# GRHV_double_30v.net
KiCad netlist of a schematic drawn in Altium Designer
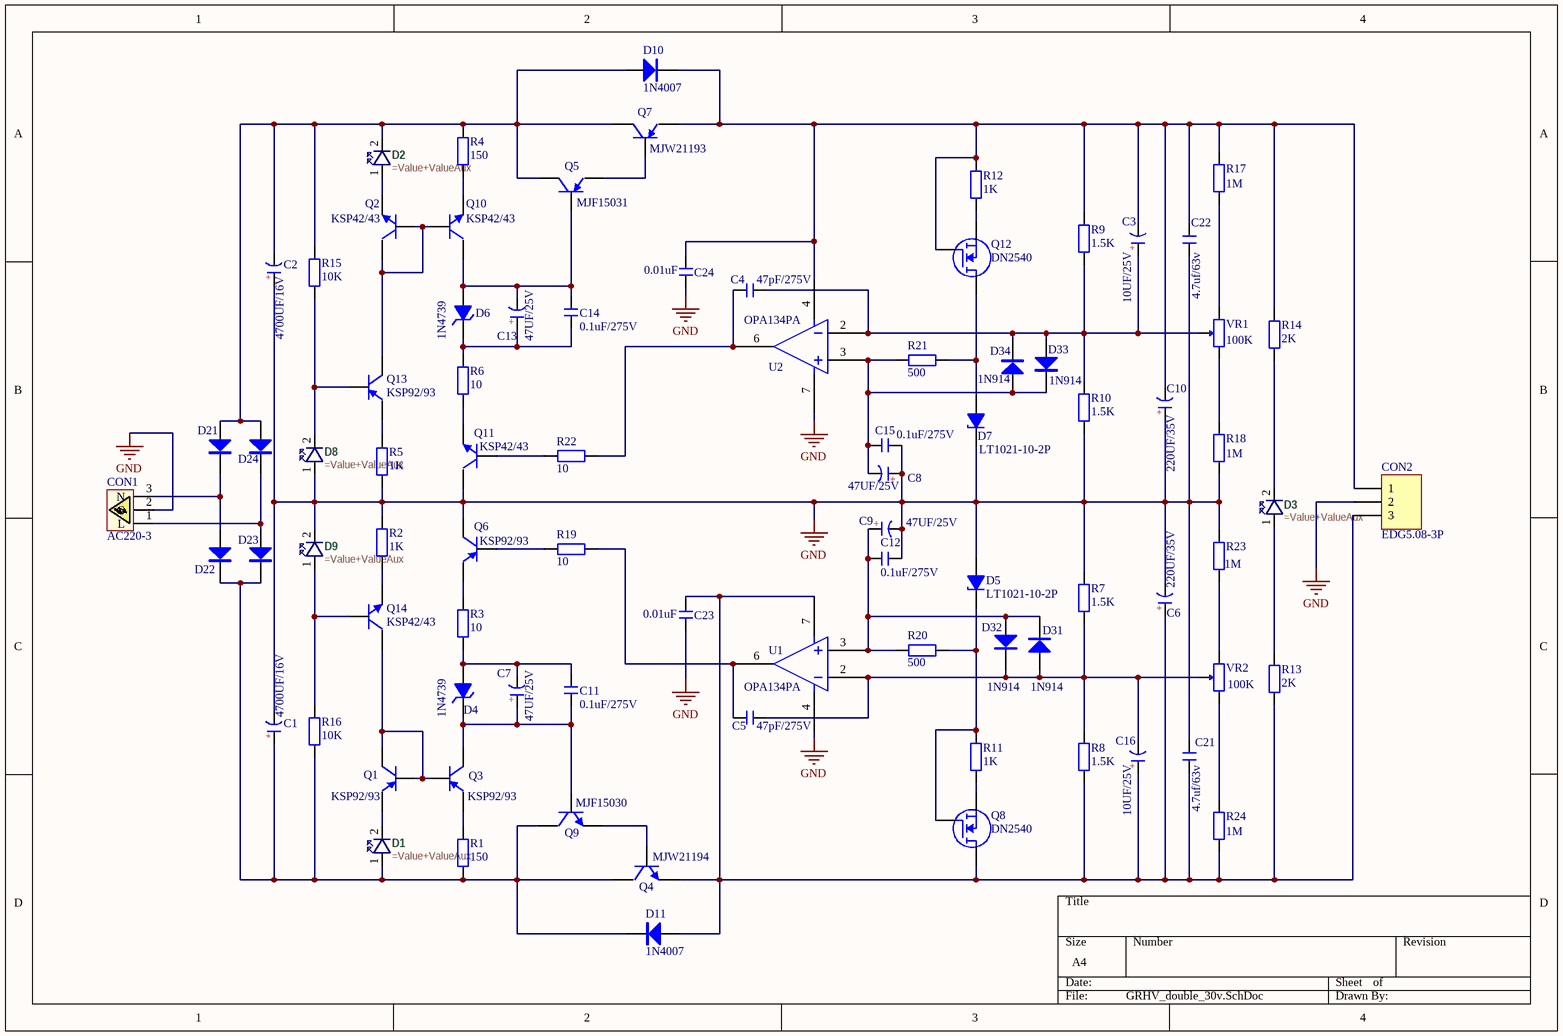
[diagram p0: GRHV_double_30v.SchDoc]

(export (version "E")
  (design (tool "Eeschema 10.0.6"))
  (components
    (comp (ref "C1")
      (value "4700UF/16V")
      (footprint "CAP 10*22*40")
      (description "直插电解电容")
      (fields (field (name "版权归属") "源创客"))
      (libsource (lib "电阻-电容-电感") (part "C-CAP"))
    )
    (comp (ref "C2")
      (value "4700UF/16V")
      (footprint "CAP 10*22*40")
      (description "直插电解电容")
      (fields (field (name "版权归属") "源创客"))
      (libsource (lib "电阻-电容-电感") (part "C-CAP"))
    )
    (comp (ref "C3")
      (value "10UF/25V")
      (footprint "CAP 2.5*6.3*7")
      (description "直插电解电容")
      (fields (field (name "版权归属") "源创客"))
      (libsource (lib "电阻-电容-电感") (part "C-CAP"))
    )
    (comp (ref "C4")
      (value "47pF/275V")
      (footprint "CBB 6.3*6.3*5")
      (description "CBB电容")
      (fields (field (name "版权归属") "源创客"))
      (libsource (lib "电阻-电容-电感") (part "C-CBB"))
    )
    (comp (ref "C5")
      (value "47pF/275V")
      (footprint "CBB 6.3*6.3*5")
      (description "CBB电容")
      (fields (field (name "版权归属") "源创客"))
      (libsource (lib "电阻-电容-电感") (part "C-CBB"))
    )
    (comp (ref "C6")
      (value "220UF/35V")
      (footprint "CAP 3.5*8*11.5")
      (description "直插电解电容")
      (fields (field (name "版权归属") "源创客"))
      (libsource (lib "电阻-电容-电感") (part "C-CAP"))
    )
    (comp (ref "C7")
      (value "47UF/25V")
      (footprint "CAP 2.5*6.3*11.2")
      (description "直插电解电容")
      (fields (field (name "版权归属") "源创客"))
      (libsource (lib "电阻-电容-电感") (part "C-CAP"))
    )
    (comp (ref "C8")
      (value "47UF/25V")
      (footprint "CAP 2.5*6.3*11.2")
      (description "直插电解电容")
      (fields (field (name "版权归属") "源创客"))
      (libsource (lib "") (part "C-CAP_1"))
    )
    (comp (ref "C9")
      (value "47UF/25V")
      (footprint "CAP 2.5*6.3*11.2")
      (description "直插电解电容")
      (fields (field (name "版权归属") "源创客"))
      (libsource (lib "") (part "C-CAP_1"))
    )
    (comp (ref "C10")
      (value "220UF/35V")
      (footprint "CAP 3.5*8*11.5")
      (description "直插电解电容")
      (fields (field (name "版权归属") "源创客"))
      (libsource (lib "电阻-电容-电感") (part "C-CAP"))
    )
    (comp (ref "C11")
      (value "0.1uF/275V")
      (footprint "CBB 6.3*6.3*5")
      (description "CBB电容")
      (fields (field (name "版权归属") "源创客"))
      (libsource (lib "电阻-电容-电感") (part "C-CBB"))
    )
    (comp (ref "C12")
      (value "0.1uF/275V")
      (footprint "CBB 6.3*6.3*5")
      (description "CBB电容")
      (fields (field (name "版权归属") "源创客"))
      (libsource (lib "电阻-电容-电感") (part "C-CBB"))
    )
    (comp (ref "C13")
      (value "47UF/25V")
      (footprint "CAP 2.5*6.3*11.2")
      (description "直插电解电容")
      (fields (field (name "版权归属") "源创客"))
      (libsource (lib "电阻-电容-电感") (part "C-CAP"))
    )
    (comp (ref "C14")
      (value "0.1uF/275V")
      (footprint "CBB 6.3*6.3*5")
      (description "CBB电容")
      (fields (field (name "版权归属") "源创客"))
      (libsource (lib "电阻-电容-电感") (part "C-CBB"))
    )
    (comp (ref "C15")
      (value "0.1uF/275V")
      (footprint "CBB 6.3*6.3*5")
      (description "CBB电容")
      (fields (field (name "版权归属") "源创客"))
      (libsource (lib "电阻-电容-电感") (part "C-CBB"))
    )
    (comp (ref "C16")
      (value "10UF/25V")
      (footprint "CAP 2.5*6.3*7")
      (description "直插电解电容")
      (fields (field (name "版权归属") "源创客"))
      (libsource (lib "电阻-电容-电感") (part "C-CAP"))
    )
    (comp (ref "C21")
      (value "4.7uf/63v")
      (footprint "CBB 7.2*7.2*13")
      (description "MKS薄膜电容")
      (libsource (lib "电阻-电容-电感") (part "C-MKS"))
    )
    (comp (ref "C22")
      (value "4.7uf/63v")
      (footprint "CBB 7.2*7.2*13")
      (description "MKS薄膜电容")
      (libsource (lib "电阻-电容-电感") (part "C-MKS"))
    )
    (comp (ref "C23")
      (value "0.01uF")
      (footprint "CBB 6.3*6.3*5")
      (description "CBB电容")
      (fields (field (name "Comment") "0.01uF/275V") (field (name "版权归属") "源创客"))
      (libsource (lib "电阻-电容-电感") (part "C-CBB"))
    )
    (comp (ref "C24")
      (value "0.01uF")
      (footprint "CBB 6.3*6.3*5")
      (description "CBB电容")
      (fields (field (name "Comment") "0.01uF/275V") (field (name "版权归属") "源创客"))
      (libsource (lib "电阻-电容-电感") (part "C-CBB"))
    )
    (comp (ref "CON1")
      (value "AC220-3")
      (footprint "HX5.08-3L")
      (libsource (lib "Connectors") (part "AC220-3"))
    )
    (comp (ref "CON2")
      (value "EDG5.08-3P")
      (footprint "HX5.08-3L")
      (libsource (lib "Connectors") (part "EDG5.08-3P"))
    )
    (comp (ref "D1")
      (value "~")
      (footprint "LED 3MM-R")
      (description "直插式LED")
      (libsource (lib "LED") (part "LED"))
    )
    (comp (ref "D2")
      (value "~")
      (footprint "LED 3MM-R")
      (description "直插式LED")
      (libsource (lib "LED") (part "LED"))
    )
    (comp (ref "D3")
      (value "~")
      (footprint "LED 3MM-R")
      (description "直插式LED")
      (libsource (lib "LED") (part "LED"))
    )
    (comp (ref "D4")
      (value "1N4739")
      (footprint "DO-41")
      (description "9.1V/1W稳压管")
      (libsource (lib "二极管-整流桥") (part "1N4739"))
    )
    (comp (ref "D5")
      (value "LT1021-10-2P")
      (footprint "DIP8-300_MH")
      (description "10V Precision Reference 2 Pin Config")
      (libsource (lib "电压参考") (part "LT1021-10-2P"))
    )
    (comp (ref "D6")
      (value "1N4739")
      (footprint "DO-41")
      (description "9.1V/1W稳压管")
      (libsource (lib "二极管-整流桥") (part "1N4739"))
    )
    (comp (ref "D7")
      (value "LT1021-10-2P")
      (footprint "DIP8-300_MH")
      (description "10V Precision Reference 2 Pin Config")
      (libsource (lib "电压参考") (part "LT1021-10-2P"))
    )
    (comp (ref "D8")
      (value "~")
      (footprint "LED 3MM-R")
      (description "直插式LED")
      (libsource (lib "LED") (part "LED"))
    )
    (comp (ref "D9")
      (value "~")
      (footprint "LED 3MM-R")
      (description "直插式LED")
      (libsource (lib "LED") (part "LED"))
    )
    (comp (ref "D10")
      (value "1N4007")
      (footprint "DO-41")
      (description "整流二极管")
      (fields (field (name "版权归属") "源创客"))
      (libsource (lib "二极管-整流桥") (part "1N4007"))
    )
    (comp (ref "D11")
      (value "1N4007")
      (footprint "DO-41")
      (description "整流二极管")
      (fields (field (name "版权归属") "源创客"))
      (libsource (lib "二极管-整流桥") (part "1N4007"))
    )
    (comp (ref "D21")
      (value "VS-HFA08TB60-M3")
      (footprint "TO220AC")
      (description "Ultrafast Soft Recovery Diado 8A 600V")
      (libsource (lib "二极管-整流桥") (part "VS-HFA08TB60-M3"))
    )
    (comp (ref "D22")
      (value "VS-HFA08TB60-M3")
      (footprint "TO220AC")
      (description "Ultrafast Soft Recovery Diado 8A 600V")
      (libsource (lib "二极管-整流桥") (part "VS-HFA08TB60-M3"))
    )
    (comp (ref "D23")
      (value "VS-HFA08TB60-M3")
      (footprint "TO220AC")
      (description "Ultrafast Soft Recovery Diado 8A 600V")
      (libsource (lib "二极管-整流桥") (part "VS-HFA08TB60-M3"))
    )
    (comp (ref "D24")
      (value "VS-HFA08TB60-M3")
      (footprint "TO220AC")
      (description "Ultrafast Soft Recovery Diado 8A 600V")
      (libsource (lib "二极管-整流桥") (part "VS-HFA08TB60-M3"))
    )
    (comp (ref "D31")
      (value "1N914")
      (footprint "DO-35")
      (description "高速开关管 1V/0.25W")
      (libsource (lib "二极管-整流桥") (part "1N914"))
    )
    (comp (ref "D32")
      (value "1N914")
      (footprint "DO-35")
      (description "高速开关管 1V/0.25W")
      (libsource (lib "二极管-整流桥") (part "1N914"))
    )
    (comp (ref "D33")
      (value "1N914")
      (footprint "DO-35")
      (description "高速开关管 1V/0.25W")
      (libsource (lib "二极管-整流桥") (part "1N914"))
    )
    (comp (ref "D34")
      (value "1N914")
      (footprint "DO-35")
      (description "高速开关管 1V/0.25W")
      (libsource (lib "二极管-整流桥") (part "1N914"))
    )
    (comp (ref "Q1")
      (value "KSP92/93")
      (footprint "TO92A")
      (description "High Voltage PNP Transistor")
      (libsource (lib "三极管") (part "KSP92/93"))
    )
    (comp (ref "Q2")
      (value "KSP42/43")
      (footprint "TO92A")
      (description "High Voltage NPN Transistor")
      (libsource (lib "三极管") (part "KSP42/43"))
    )
    (comp (ref "Q3")
      (value "KSP92/93")
      (footprint "TO92A")
      (description "High Voltage PNP Transistor")
      (libsource (lib "三极管") (part "KSP92/93"))
    )
    (comp (ref "Q4")
      (value "MJW21194")
      (footprint "TO247V")
      (description "Power NPN Transistor")
      (libsource (lib "三极管") (part "MJW21194"))
    )
    (comp (ref "Q5")
      (value "MJF15031")
      (footprint "TO220V")
      (description "Power PNP Transistor")
      (libsource (lib "三极管") (part "MJF15031"))
    )
    (comp (ref "Q6")
      (value "KSP92/93")
      (footprint "TO92A")
      (description "High Voltage PNP Transistor")
      (libsource (lib "三极管") (part "KSP92/93"))
    )
    (comp (ref "Q7")
      (value "MJW21193")
      (footprint "TO247V")
      (description "Power PNP Transistor")
      (libsource (lib "三极管") (part "MJW21193"))
    )
    (comp (ref "Q8")
      (value "DN2540")
      (footprint "TO92A")
      (description "N沟道耗尽型DMOS场效应管 400V/150ma")
      (libsource (lib "场效应管") (part "DN2540"))
    )
    (comp (ref "Q9")
      (value "MJF15030")
      (footprint "TO220V")
      (description "Power NPN Transistor")
      (libsource (lib "三极管") (part "MJF15030"))
    )
    (comp (ref "Q10")
      (value "KSP42/43")
      (footprint "TO92A")
      (description "High Voltage NPN Transistor")
      (libsource (lib "三极管") (part "KSP42/43"))
    )
    (comp (ref "Q11")
      (value "KSP42/43")
      (footprint "TO92A")
      (description "High Voltage NPN Transistor")
      (libsource (lib "三极管") (part "KSP42/43"))
    )
    (comp (ref "Q12")
      (value "DN2540")
      (footprint "TO92A")
      (description "N沟道耗尽型DMOS场效应管 400V/150ma")
      (libsource (lib "场效应管") (part "DN2540"))
    )
    (comp (ref "Q13")
      (value "KSP92/93")
      (footprint "TO92A")
      (description "High Voltage PNP Transistor")
      (libsource (lib "三极管") (part "KSP92/93"))
    )
    (comp (ref "Q14")
      (value "KSP42/43")
      (footprint "TO92A")
      (description "High Voltage NPN Transistor")
      (libsource (lib "三极管") (part "KSP42/43"))
    )
    (comp (ref "R1")
      (value "150")
      (footprint "RS 1/4W")
      (description "直插色环电阻")
      (fields (field (name "版权归属") "源创客"))
      (libsource (lib "电阻-电容-电感") (part "R-CRR"))
    )
    (comp (ref "R2")
      (value "1K")
      (footprint "RS 1/4W")
      (description "直插色环电阻")
      (fields (field (name "版权归属") "源创客"))
      (libsource (lib "电阻-电容-电感") (part "R-CRR"))
    )
    (comp (ref "R3")
      (value "10")
      (footprint "RS 1/4W")
      (description "直插色环电阻")
      (fields (field (name "版权归属") "源创客"))
      (libsource (lib "电阻-电容-电感") (part "R-CRR"))
    )
    (comp (ref "R4")
      (value "150")
      (footprint "RS 1/4W")
      (description "直插色环电阻")
      (fields (field (name "版权归属") "源创客"))
      (libsource (lib "电阻-电容-电感") (part "R-CRR"))
    )
    (comp (ref "R5")
      (value "1K")
      (footprint "RS 1/4W")
      (description "直插色环电阻")
      (fields (field (name "版权归属") "源创客"))
      (libsource (lib "电阻-电容-电感") (part "R-CRR"))
    )
    (comp (ref "R6")
      (value "10")
      (footprint "RS 1/4W")
      (description "直插色环电阻")
      (fields (field (name "版权归属") "源创客"))
      (libsource (lib "电阻-电容-电感") (part "R-CRR"))
    )
    (comp (ref "R7")
      (value "1.5K")
      (footprint "RS 1/4W")
      (description "直插色环电阻")
      (fields (field (name "版权归属") "源创客"))
      (libsource (lib "电阻-电容-电感") (part "R-CRR"))
    )
    (comp (ref "R8")
      (value "1.5K")
      (footprint "RS 1/4W")
      (description "直插色环电阻")
      (fields (field (name "版权归属") "源创客"))
      (libsource (lib "电阻-电容-电感") (part "R-CRR"))
    )
    (comp (ref "R9")
      (value "1.5K")
      (footprint "RS 1/4W")
      (description "直插色环电阻")
      (fields (field (name "版权归属") "源创客"))
      (libsource (lib "电阻-电容-电感") (part "R-CRR"))
    )
    (comp (ref "R10")
      (value "1.5K")
      (footprint "RS 1/4W")
      (description "直插色环电阻")
      (fields (field (name "版权归属") "源创客"))
      (libsource (lib "电阻-电容-电感") (part "R-CRR"))
    )
    (comp (ref "R11")
      (value "1K")
      (footprint "RS 1/4W")
      (description "直插色环电阻")
      (fields (field (name "版权归属") "源创客"))
      (libsource (lib "电阻-电容-电感") (part "R-CRR"))
    )
    (comp (ref "R12")
      (value "1K")
      (footprint "RS 1/4W")
      (description "直插色环电阻")
      (fields (field (name "版权归属") "源创客"))
      (libsource (lib "电阻-电容-电感") (part "R-CRR"))
    )
    (comp (ref "R13")
      (value "2K")
      (footprint "RS 1/4W")
      (description "直插色环电阻")
      (fields (field (name "版权归属") "源创客"))
      (libsource (lib "电阻-电容-电感") (part "R-CRR"))
    )
    (comp (ref "R14")
      (value "2K")
      (footprint "RS 1/4W")
      (description "直插色环电阻")
      (fields (field (name "版权归属") "源创客"))
      (libsource (lib "电阻-电容-电感") (part "R-CRR"))
    )
    (comp (ref "R15")
      (value "10K")
      (footprint "RS 1/4W")
      (description "直插色环电阻")
      (fields (field (name "版权归属") "源创客"))
      (libsource (lib "电阻-电容-电感") (part "R-CRR"))
    )
    (comp (ref "R16")
      (value "10K")
      (footprint "RS 1/4W")
      (description "直插色环电阻")
      (fields (field (name "版权归属") "源创客"))
      (libsource (lib "电阻-电容-电感") (part "R-CRR"))
    )
    (comp (ref "R17")
      (value "1M")
      (footprint "RS 1/4W")
      (description "直插色环电阻")
      (fields (field (name "版权归属") "源创客"))
      (libsource (lib "电阻-电容-电感") (part "R-CRR"))
    )
    (comp (ref "R18")
      (value "1M")
      (footprint "RS 1/4W")
      (description "直插色环电阻")
      (fields (field (name "版权归属") "源创客"))
      (libsource (lib "电阻-电容-电感") (part "R-CRR"))
    )
    (comp (ref "R19")
      (value "10")
      (footprint "RS 1/4W")
      (description "直插色环电阻")
      (fields (field (name "版权归属") "源创客"))
      (libsource (lib "电阻-电容-电感") (part "R-CRR"))
    )
    (comp (ref "R20")
      (value "500")
      (footprint "RS 1/4W")
      (description "直插色环电阻")
      (fields (field (name "版权归属") "源创客"))
      (libsource (lib "电阻-电容-电感") (part "R-CRR"))
    )
    (comp (ref "R21")
      (value "500")
      (footprint "RS 1/4W")
      (description "直插色环电阻")
      (fields (field (name "版权归属") "源创客"))
      (libsource (lib "电阻-电容-电感") (part "R-CRR"))
    )
    (comp (ref "R22")
      (value "10")
      (footprint "RS 1/4W")
      (description "直插色环电阻")
      (fields (field (name "版权归属") "源创客"))
      (libsource (lib "电阻-电容-电感") (part "R-CRR"))
    )
    (comp (ref "R23")
      (value "1M")
      (footprint "RS 1/4W")
      (description "直插色环电阻")
      (fields (field (name "版权归属") "源创客"))
      (libsource (lib "电阻-电容-电感") (part "R-CRR"))
    )
    (comp (ref "R24")
      (value "1M")
      (footprint "RS 1/4W")
      (description "直插色环电阻")
      (fields (field (name "版权归属") "源创客"))
      (libsource (lib "电阻-电容-电感") (part "R-CRR"))
    )
    (comp (ref "U1") (value "OPA134PA") (footprint "DIP8-300_MH") (libsource (lib "运放") (part "OPA134PA")))
    (comp (ref "U2") (value "OPA134PA") (footprint "DIP8-300_MH") (libsource (lib "运放") (part "OPA134PA")))
    (comp (ref "VR1")
      (value "100K")
      (footprint "RS 1/2W-VR")
      (description "直插可调电阻-顶调")
      (fields (field (name "Comment") "VR-W"))
      (libsource (lib "电阻-电容-电感") (part "VR-W"))
    )
    (comp (ref "VR2")
      (value "100K")
      (footprint "RS 1/2W-VR")
      (description "直插可调电阻-顶调")
      (fields (field (name "Comment") "VR-W"))
      (libsource (lib "电阻-电容-电感") (part "VR-W"))
    )
  )
  (nets
    (net (code "1") (name "GND") (class "Default")
      (node (ref "C1") (pin "2") (pinfunction "K_2") (pintype "passive"))
      (node (ref "C10") (pin "1") (pinfunction "A_1") (pintype "passive"))
      (node (ref "C12") (pin "2") (pinfunction "2_2") (pintype "passive"))
      (node (ref "C15") (pin "2") (pinfunction "2_2") (pintype "passive"))
      (node (ref "C2") (pin "1") (pinfunction "A_1") (pintype "passive"))
      (node (ref "C21") (pin "2") (pinfunction "2_2") (pintype "passive"))
      (node (ref "C22") (pin "1") (pinfunction "1_1") (pintype "passive"))
      (node (ref "C23") (pin "1") (pinfunction "1_1") (pintype "passive"))
      (node (ref "C24") (pin "1") (pinfunction "1_1") (pintype "passive"))
      (node (ref "C6") (pin "2") (pinfunction "K_2") (pintype "passive"))
      (node (ref "C8") (pin "1") (pinfunction "A_1") (pintype "passive"))
      (node (ref "C9") (pin "2") (pinfunction "K_2") (pintype "passive"))
      (node (ref "CON1") (pin "2") (pinfunction "G_2") (pintype "passive"))
      (node (ref "CON2") (pin "2") (pinfunction "2_2") (pintype "passive"))
      (node (ref "D5") (pin "4") (pinfunction "A_4") (pintype "passive"))
      (node (ref "D7") (pin "6") (pinfunction "K_6") (pintype "passive"))
      (node (ref "D8") (pin "1") (pinfunction "A_1") (pintype "passive"))
      (node (ref "D9") (pin "2") (pinfunction "K_2") (pintype "passive"))
      (node (ref "Q11") (pin "3") (pinfunction "C_3") (pintype "passive"))
      (node (ref "Q6") (pin "3") (pinfunction "C_3") (pintype "passive"))
      (node (ref "R10") (pin "1") (pinfunction "1_1") (pintype "passive"))
      (node (ref "R18") (pin "1") (pinfunction "1_1") (pintype "passive"))
      (node (ref "R2") (pin "2") (pinfunction "2_2") (pintype "passive"))
      (node (ref "R23") (pin "2") (pinfunction "2_2") (pintype "passive"))
      (node (ref "R5") (pin "1") (pinfunction "1_1") (pintype "passive"))
      (node (ref "R7") (pin "2") (pinfunction "2_2") (pintype "passive"))
      (node (ref "U1") (pin "4") (pinfunction "V-_4") (pintype "passive"))
      (node (ref "U2") (pin "7") (pinfunction "V+_7") (pintype "passive"))
    )
    (net (code "2") (name "Net-(C1-A)") (class "Default")
      (node (ref "C1") (pin "1") (pinfunction "A_1") (pintype "passive"))
      (node (ref "D1") (pin "1") (pinfunction "A_1") (pintype "passive"))
      (node (ref "D11") (pin "2") (pinfunction "K_2") (pintype "passive"))
      (node (ref "D22") (pin "1") (pinfunction "Cathode_1") (pintype "passive"))
      (node (ref "D23") (pin "1") (pinfunction "Cathode_1") (pintype "passive"))
      (node (ref "Q4") (pin "2") (pinfunction "C_2") (pintype "passive"))
      (node (ref "Q9") (pin "2") (pinfunction "C_2") (pintype "passive"))
      (node (ref "R1") (pin "1") (pinfunction "1_1") (pintype "passive"))
      (node (ref "R16") (pin "1") (pinfunction "1_1") (pintype "passive"))
    )
    (net (code "3") (name "Net-(C2-K)") (class "Default")
      (node (ref "C2") (pin "2") (pinfunction "K_2") (pintype "passive"))
      (node (ref "D10") (pin "1") (pinfunction "A_1") (pintype "passive"))
      (node (ref "D2") (pin "2") (pinfunction "K_2") (pintype "passive"))
      (node (ref "D21") (pin "2") (pinfunction "Anode_2") (pintype "passive"))
      (node (ref "D24") (pin "2") (pinfunction "Anode_2") (pintype "passive"))
      (node (ref "Q5") (pin "2") (pinfunction "C_2") (pintype "passive"))
      (node (ref "Q7") (pin "2") (pinfunction "C_2") (pintype "passive"))
      (node (ref "R15") (pin "2") (pinfunction "2_2") (pintype "passive"))
      (node (ref "R4") (pin "2") (pinfunction "2_2") (pintype "passive"))
    )
    (net (code "4") (name "Net-(C3-A)") (class "Default")
      (node (ref "C3") (pin "1") (pinfunction "A_1") (pintype "passive"))
      (node (ref "C4") (pin "2") (pinfunction "2_2") (pintype "passive"))
      (node (ref "D33") (pin "1") (pinfunction "A_1") (pintype "passive"))
      (node (ref "D34") (pin "2") (pinfunction "K_2") (pintype "passive"))
      (node (ref "R10") (pin "2") (pinfunction "2_2") (pintype "passive"))
      (node (ref "R9") (pin "1") (pinfunction "1_1") (pintype "passive"))
      (node (ref "U2") (pin "2") (pinfunction "-in_2") (pintype "passive"))
      (node (ref "VR1") (pin "3") (pinfunction "3_3") (pintype "passive"))
    )
    (net (code "5") (name "Net-(C7-A)") (class "Default")
      (node (ref "C11") (pin "1") (pinfunction "1_1") (pintype "passive"))
      (node (ref "C7") (pin "1") (pinfunction "A_1") (pintype "passive"))
      (node (ref "D4") (pin "2") (pinfunction "K_2") (pintype "passive"))
      (node (ref "Q3") (pin "3") (pinfunction "C_3") (pintype "passive"))
      (node (ref "Q9") (pin "1") (pinfunction "B_1") (pintype "passive"))
    )
    (net (code "6") (name "Net-(C7-K)") (class "Default")
      (node (ref "C11") (pin "2") (pinfunction "2_2") (pintype "passive"))
      (node (ref "C7") (pin "2") (pinfunction "K_2") (pintype "passive"))
      (node (ref "D4") (pin "1") (pinfunction "A_1") (pintype "passive"))
      (node (ref "R3") (pin "1") (pinfunction "1_1") (pintype "passive"))
    )
    (net (code "7") (name "Net-(C8-K)") (class "Default")
      (node (ref "C15") (pin "1") (pinfunction "1_1") (pintype "passive"))
      (node (ref "C8") (pin "2") (pinfunction "K_2") (pintype "passive"))
      (node (ref "D33") (pin "2") (pinfunction "K_2") (pintype "passive"))
      (node (ref "D34") (pin "1") (pinfunction "A_1") (pintype "passive"))
      (node (ref "R21") (pin "1") (pinfunction "1_1") (pintype "passive"))
      (node (ref "U2") (pin "3") (pinfunction "+in_3") (pintype "passive"))
    )
    (net (code "8") (name "Net-(C9-A)") (class "Default")
      (node (ref "C12") (pin "1") (pinfunction "1_1") (pintype "passive"))
      (node (ref "C9") (pin "1") (pinfunction "A_1") (pintype "passive"))
      (node (ref "D31") (pin "2") (pinfunction "K_2") (pintype "passive"))
      (node (ref "D32") (pin "1") (pinfunction "A_1") (pintype "passive"))
      (node (ref "R20") (pin "1") (pinfunction "1_1") (pintype "passive"))
      (node (ref "U1") (pin "3") (pinfunction "+in_3") (pintype "passive"))
    )
    (net (code "9") (name "Net-(C10-K)") (class "Default")
      (node (ref "C10") (pin "2") (pinfunction "K_2") (pintype "passive"))
      (node (ref "C22") (pin "2") (pinfunction "2_2") (pintype "passive"))
      (node (ref "C24") (pin "2") (pinfunction "2_2") (pintype "passive"))
      (node (ref "C3") (pin "2") (pinfunction "K_2") (pintype "passive"))
      (node (ref "CON2") (pin "1") (pinfunction "1_1") (pintype "passive"))
      (node (ref "D10") (pin "2") (pinfunction "K_2") (pintype "passive"))
      (node (ref "Q12") (pin "2") (pinfunction "G_2") (pintype "passive"))
      (node (ref "Q7") (pin "3") (pinfunction "E_3") (pintype "passive"))
      (node (ref "R12") (pin "2") (pinfunction "2_2") (pintype "passive"))
      (node (ref "R14") (pin "2") (pinfunction "2_2") (pintype "passive"))
      (node (ref "R17") (pin "2") (pinfunction "2_2") (pintype "passive"))
      (node (ref "R9") (pin "2") (pinfunction "2_2") (pintype "passive"))
      (node (ref "U2") (pin "4") (pinfunction "V-_4") (pintype "passive"))
    )
    (net (code "10") (name "Net-(C13-A)") (class "Default")
      (node (ref "C13") (pin "1") (pinfunction "A_1") (pintype "passive"))
      (node (ref "C14") (pin "1") (pinfunction "1_1") (pintype "passive"))
      (node (ref "D6") (pin "2") (pinfunction "K_2") (pintype "passive"))
      (node (ref "R6") (pin "2") (pinfunction "2_2") (pintype "passive"))
    )
    (net (code "11") (name "Net-(C13-K)") (class "Default")
      (node (ref "C13") (pin "2") (pinfunction "K_2") (pintype "passive"))
      (node (ref "C14") (pin "2") (pinfunction "2_2") (pintype "passive"))
      (node (ref "D6") (pin "1") (pinfunction "A_1") (pintype "passive"))
      (node (ref "Q10") (pin "3") (pinfunction "C_3") (pintype "passive"))
      (node (ref "Q5") (pin "1") (pinfunction "B_1") (pintype "passive"))
    )
    (net (code "12") (name "Net-(C16-A)") (class "Default")
      (node (ref "C16") (pin "1") (pinfunction "A_1") (pintype "passive"))
      (node (ref "C21") (pin "1") (pinfunction "1_1") (pintype "passive"))
      (node (ref "C23") (pin "2") (pinfunction "2_2") (pintype "passive"))
      (node (ref "C6") (pin "1") (pinfunction "A_1") (pintype "passive"))
      (node (ref "CON2") (pin "3") (pinfunction "3_3") (pintype "passive"))
      (node (ref "D11") (pin "1") (pinfunction "A_1") (pintype "passive"))
      (node (ref "Q4") (pin "3") (pinfunction "E_3") (pintype "passive"))
      (node (ref "Q8") (pin "3") (pinfunction "D_3") (pintype "passive"))
      (node (ref "R13") (pin "2") (pinfunction "2_2") (pintype "passive"))
      (node (ref "R24") (pin "1") (pinfunction "1_1") (pintype "passive"))
      (node (ref "R8") (pin "1") (pinfunction "1_1") (pintype "passive"))
      (node (ref "U1") (pin "7") (pinfunction "V+_7") (pintype "passive"))
    )
    (net (code "13") (name "Net-(C16-K)") (class "Default")
      (node (ref "C16") (pin "2") (pinfunction "K_2") (pintype "passive"))
      (node (ref "C5") (pin "2") (pinfunction "2_2") (pintype "passive"))
      (node (ref "D31") (pin "1") (pinfunction "A_1") (pintype "passive"))
      (node (ref "D32") (pin "2") (pinfunction "K_2") (pintype "passive"))
      (node (ref "R7") (pin "1") (pinfunction "1_1") (pintype "passive"))
      (node (ref "R8") (pin "2") (pinfunction "2_2") (pintype "passive"))
      (node (ref "U1") (pin "2") (pinfunction "-in_2") (pintype "passive"))
      (node (ref "VR2") (pin "3") (pinfunction "3_3") (pintype "passive"))
    )
    (net (code "14") (name "Net-(CON1-L)") (class "Default")
      (node (ref "CON1") (pin "1") (pinfunction "L_1") (pintype "passive"))
      (node (ref "D23") (pin "2") (pinfunction "Anode_2") (pintype "passive"))
      (node (ref "D24") (pin "1") (pinfunction "Cathode_1") (pintype "passive"))
    )
    (net (code "15") (name "Net-(CON1-N)") (class "Default")
      (node (ref "CON1") (pin "3") (pinfunction "N_3") (pintype "passive"))
      (node (ref "D21") (pin "1") (pinfunction "Cathode_1") (pintype "passive"))
      (node (ref "D22") (pin "2") (pinfunction "Anode_2") (pintype "passive"))
    )
    (net (code "16") (name "Net-(D1-K)") (class "Default")
      (node (ref "D1") (pin "2") (pinfunction "K_2") (pintype "passive"))
      (node (ref "Q1") (pin "1") (pinfunction "E_1") (pintype "passive"))
    )
    (net (code "17") (name "Net-(D2-A)") (class "Default")
      (node (ref "D2") (pin "1") (pinfunction "A_1") (pintype "passive"))
      (node (ref "Q2") (pin "1") (pinfunction "E_1") (pintype "passive"))
    )
    (net (code "18") (name "Net-(D3-A)") (class "Default")
      (node (ref "D3") (pin "1") (pinfunction "A_1") (pintype "passive"))
      (node (ref "R13") (pin "1") (pinfunction "1_1") (pintype "passive"))
    )
    (net (code "19") (name "Net-(D3-K)") (class "Default")
      (node (ref "D3") (pin "2") (pinfunction "K_2") (pintype "passive"))
      (node (ref "R14") (pin "1") (pinfunction "1_1") (pintype "passive"))
    )
    (net (code "20") (name "Net-(D5-K)") (class "Default")
      (node (ref "D5") (pin "6") (pinfunction "K_6") (pintype "passive"))
      (node (ref "Q8") (pin "2") (pinfunction "G_2") (pintype "passive"))
      (node (ref "R11") (pin "2") (pinfunction "2_2") (pintype "passive"))
      (node (ref "R20") (pin "2") (pinfunction "2_2") (pintype "passive"))
    )
    (net (code "21") (name "Net-(D7-A)") (class "Default")
      (node (ref "D7") (pin "4") (pinfunction "A_4") (pintype "passive"))
      (node (ref "Q12") (pin "3") (pinfunction "D_3") (pintype "passive"))
      (node (ref "R21") (pin "2") (pinfunction "2_2") (pintype "passive"))
    )
    (net (code "22") (name "Net-(D8-K)") (class "Default")
      (node (ref "D8") (pin "2") (pinfunction "K_2") (pintype "passive"))
      (node (ref "Q13") (pin "2") (pinfunction "B_2") (pintype "passive"))
      (node (ref "R15") (pin "1") (pinfunction "1_1") (pintype "passive"))
    )
    (net (code "23") (name "Net-(D9-A)") (class "Default")
      (node (ref "D9") (pin "1") (pinfunction "A_1") (pintype "passive"))
      (node (ref "Q14") (pin "2") (pinfunction "B_2") (pintype "passive"))
      (node (ref "R16") (pin "2") (pinfunction "2_2") (pintype "passive"))
    )
    (net (code "24") (name "Net-(Q1-B)") (class "Default")
      (node (ref "Q1") (pin "2") (pinfunction "B_2") (pintype "passive"))
      (node (ref "Q1") (pin "3") (pinfunction "C_3") (pintype "passive"))
      (node (ref "Q14") (pin "3") (pinfunction "C_3") (pintype "passive"))
      (node (ref "Q3") (pin "2") (pinfunction "B_2") (pintype "passive"))
    )
    (net (code "25") (name "Net-(Q3-E)") (class "Default")
      (node (ref "Q3") (pin "1") (pinfunction "E_1") (pintype "passive"))
      (node (ref "R1") (pin "2") (pinfunction "2_2") (pintype "passive"))
    )
    (net (code "26") (name "Net-(Q4-B)") (class "Default")
      (node (ref "Q4") (pin "1") (pinfunction "B_1") (pintype "passive"))
      (node (ref "Q9") (pin "3") (pinfunction "E_3") (pintype "passive"))
    )
    (net (code "27") (name "Net-(Q5-E)") (class "Default")
      (node (ref "Q5") (pin "3") (pinfunction "E_3") (pintype "passive"))
      (node (ref "Q7") (pin "1") (pinfunction "B_1") (pintype "passive"))
    )
    (net (code "28") (name "Net-(Q6-B)") (class "Default")
      (node (ref "Q6") (pin "2") (pinfunction "B_2") (pintype "passive"))
      (node (ref "R19") (pin "1") (pinfunction "1_1") (pintype "passive"))
    )
    (net (code "29") (name "Net-(Q6-E)") (class "Default")
      (node (ref "Q6") (pin "1") (pinfunction "E_1") (pintype "passive"))
      (node (ref "R3") (pin "2") (pinfunction "2_2") (pintype "passive"))
    )
    (net (code "30") (name "Net-(Q8-S)") (class "Default")
      (node (ref "Q8") (pin "1") (pinfunction "S_1") (pintype "passive"))
      (node (ref "R11") (pin "1") (pinfunction "1_1") (pintype "passive"))
    )
    (net (code "31") (name "Net-(Q10-B)") (class "Default")
      (node (ref "Q10") (pin "2") (pinfunction "B_2") (pintype "passive"))
      (node (ref "Q13") (pin "3") (pinfunction "C_3") (pintype "passive"))
      (node (ref "Q2") (pin "2") (pinfunction "B_2") (pintype "passive"))
      (node (ref "Q2") (pin "3") (pinfunction "C_3") (pintype "passive"))
    )
    (net (code "32") (name "Net-(Q10-E)") (class "Default")
      (node (ref "Q10") (pin "1") (pinfunction "E_1") (pintype "passive"))
      (node (ref "R4") (pin "1") (pinfunction "1_1") (pintype "passive"))
    )
    (net (code "33") (name "Net-(Q11-B)") (class "Default")
      (node (ref "Q11") (pin "2") (pinfunction "B_2") (pintype "passive"))
      (node (ref "R22") (pin "1") (pinfunction "1_1") (pintype "passive"))
    )
    (net (code "34") (name "Net-(Q11-E)") (class "Default")
      (node (ref "Q11") (pin "1") (pinfunction "E_1") (pintype "passive"))
      (node (ref "R6") (pin "1") (pinfunction "1_1") (pintype "passive"))
    )
    (net (code "35") (name "Net-(Q12-S)") (class "Default")
      (node (ref "Q12") (pin "1") (pinfunction "S_1") (pintype "passive"))
      (node (ref "R12") (pin "1") (pinfunction "1_1") (pintype "passive"))
    )
    (net (code "36") (name "Net-(Q13-E)") (class "Default")
      (node (ref "Q13") (pin "1") (pinfunction "E_1") (pintype "passive"))
      (node (ref "R5") (pin "2") (pinfunction "2_2") (pintype "passive"))
    )
    (net (code "37") (name "Net-(Q14-E)") (class "Default")
      (node (ref "Q14") (pin "1") (pinfunction "E_1") (pintype "passive"))
      (node (ref "R2") (pin "1") (pinfunction "1_1") (pintype "passive"))
    )
    (net (code "38") (name "Net-(R17-Pad1)") (class "Default")
      (node (ref "R17") (pin "1") (pinfunction "1_1") (pintype "passive"))
      (node (ref "VR1") (pin "2") (pinfunction "2_2") (pintype "passive"))
    )
    (net (code "39") (name "Net-(R18-Pad2)") (class "Default")
      (node (ref "R18") (pin "2") (pinfunction "2_2") (pintype "passive"))
      (node (ref "VR1") (pin "1") (pinfunction "1_1") (pintype "passive"))
    )
    (net (code "40") (name "Net-(R23-Pad1)") (class "Default")
      (node (ref "R23") (pin "1") (pinfunction "1_1") (pintype "passive"))
      (node (ref "VR2") (pin "2") (pinfunction "2_2") (pintype "passive"))
    )
    (net (code "41") (name "Net-(R24-Pad2)") (class "Default")
      (node (ref "R24") (pin "2") (pinfunction "2_2") (pintype "passive"))
      (node (ref "VR2") (pin "1") (pinfunction "1_1") (pintype "passive"))
    )
    (net (code "42") (name "Net-(U1-out)") (class "Default")
      (node (ref "C5") (pin "1") (pinfunction "1_1") (pintype "passive"))
      (node (ref "R19") (pin "2") (pinfunction "2_2") (pintype "passive"))
      (node (ref "U1") (pin "6") (pinfunction "out_6") (pintype "passive"))
    )
    (net (code "43") (name "Net-(U2-out)") (class "Default")
      (node (ref "C4") (pin "1") (pinfunction "1_1") (pintype "passive"))
      (node (ref "R22") (pin "2") (pinfunction "2_2") (pintype "passive"))
      (node (ref "U2") (pin "6") (pinfunction "out_6") (pintype "passive"))
    )
  )
)
